# Conectors_IsolatedSupply.net
KiCad netlist of a schematic drawn in Altium Designer
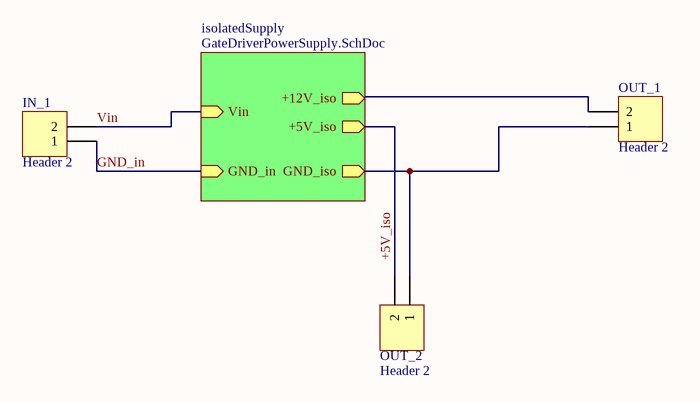
[diagram p0: Conectors_IsolatedSupply.SchDoc]

(export (version "E")
  (design (tool "Eeschema 10.0.6"))
  (components
    (comp (ref "IN_1")
      (value "Header 2")
      (footprint "Header2")
      (description "Header, 2-Pin")
      (libsource (lib "Miscellaneous Connectors") (part "Header 2"))
    )
    (comp (ref "OUT_1")
      (value "Header 2")
      (footprint "Header2")
      (description "Header, 2-Pin")
      (libsource (lib "") (part "Header 2_2"))
    )
    (comp (ref "OUT_2")
      (value "Header 2")
      (footprint "Header2")
      (description "Header, 2-Pin")
      (libsource (lib "") (part "Header 2_1"))
    )
  )
  (nets
    (net (code "1") (name "/+5V_iso") (class "Default")
      (node (ref "OUT_2") (pin "2") (pinfunction "2_2") (pintype "passive"))
    )
    (net (code "3") (name "/GND_in") (class "Default")
      (node (ref "IN_1") (pin "1") (pinfunction "1_1") (pintype "passive"))
    )
    (net (code "4") (name "/GND_iso") (class "Default")
      (node (ref "OUT_1") (pin "1") (pinfunction "1_1") (pintype "passive"))
      (node (ref "OUT_2") (pin "1") (pinfunction "1_1") (pintype "passive"))
    )
    (net (code "5") (name "/Vin") (class "Default")
      (node (ref "IN_1") (pin "2") (pinfunction "2_2") (pintype "passive"))
    )
    (net (code "6") (name "unconnected-(OUT_1-Pad2)") (class "Default")
      (node (ref "OUT_1") (pin "2") (pinfunction "2_2") (pintype "passive"))
    )
  )
)
